# Sheet.net
KiCad netlist of a schematic drawn in Altium Designer
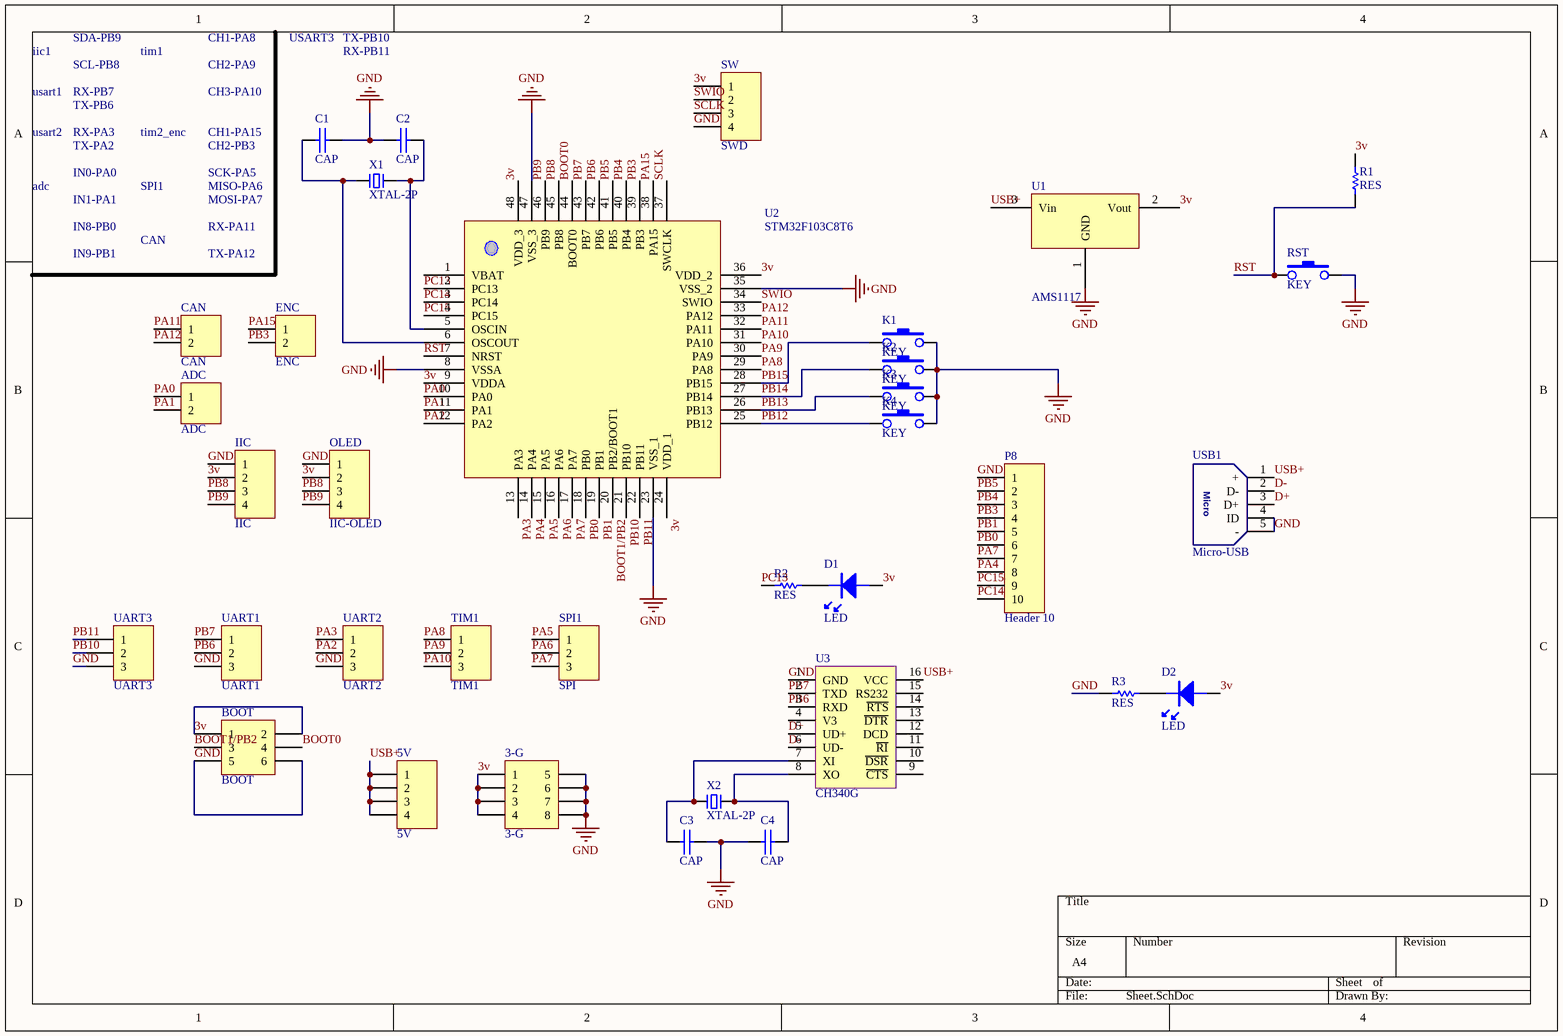
[diagram p0: Sheet.SchDoc]

(export (version "E")
  (design (tool "Eeschema 10.0.6"))
  (components
    (comp (ref "3-G")
      (value "3-G")
      (footprint "HDR2X4_CEN")
      (description "Header, 4-Pin, Dual row")
      (fields (field (name "PUBLISHER") "Altium Limited"))
      (libsource (lib "Miscellaneous Connectors") (part "Header 4X2A"))
    )
    (comp (ref "5V")
      (value "5V")
      (footprint "HDR1X4")
      (description "Header, 4-Pin")
      (fields (field (name "PUBLISHER") "Altium Limited"))
      (libsource (lib "Miscellaneous Connectors") (part "Header 4"))
    )
    (comp (ref "ADC")
      (value "ADC")
      (footprint "HDR1X2")
      (description "Header, 2-Pin")
      (fields (field (name "PUBLISHER") "Altium Limited"))
      (libsource (lib "Miscellaneous Connectors") (part "Header 2"))
    )
    (comp (ref "BOOT")
      (value "BOOT")
      (footprint "HDR2X3")
      (description "Header, 3-Pin, Dual row")
      (fields (field (name "PUBLISHER") "Altium Limited"))
      (libsource (lib "Miscellaneous Connectors") (part "Header 3X2"))
    )
    (comp (ref "C1")
      (value "CAP")
      (footprint "0603C")
      (description "无极性电容")
      (libsource (lib "电容") (part "CAP"))
    )
    (comp (ref "C2")
      (value "CAP")
      (footprint "0603C")
      (description "无极性电容")
      (libsource (lib "电容") (part "CAP"))
    )
    (comp (ref "C3")
      (value "CAP")
      (footprint "0603C")
      (description "无极性电容")
      (libsource (lib "电容") (part "CAP"))
    )
    (comp (ref "C4")
      (value "CAP")
      (footprint "0603C")
      (description "无极性电容")
      (libsource (lib "电容") (part "CAP"))
    )
    (comp (ref "CAN")
      (value "CAN")
      (footprint "HDR1X2")
      (description "Header, 2-Pin")
      (fields (field (name "PUBLISHER") "Altium Limited"))
      (libsource (lib "Miscellaneous Connectors") (part "Header 2"))
    )
    (comp (ref "D1") (value "LED") (footprint "LED-0603B") (libsource (lib "LED") (part "LED")))
    (comp (ref "D2") (value "LED") (footprint "LED-0603B") (libsource (lib "LED") (part "LED")))
    (comp (ref "ENC")
      (value "ENC")
      (footprint "HDR1X2")
      (description "Header, 2-Pin")
      (fields (field (name "PUBLISHER") "Altium Limited"))
      (libsource (lib "Miscellaneous Connectors") (part "Header 2"))
    )
    (comp (ref "IIC")
      (value "IIC")
      (footprint "HDR1X4")
      (description "Header, 4-Pin")
      (fields (field (name "PUBLISHER") "Altium Limited"))
      (libsource (lib "Miscellaneous Connectors") (part "Header 4"))
    )
    (comp (ref "K1") (value "KEY") (footprint "DIP-3X6X4.3") (libsource (lib "轻触开关") (part "KEY")))
    (comp (ref "K2") (value "KEY") (footprint "DIP-3X6X4.3") (libsource (lib "轻触开关") (part "KEY")))
    (comp (ref "K3") (value "KEY") (footprint "DIP-3X6X4.3") (libsource (lib "轻触开关") (part "KEY")))
    (comp (ref "K4") (value "KEY") (footprint "DIP-3X6X4.3") (libsource (lib "轻触开关") (part "KEY")))
    (comp (ref "OLED")
      (value "IIC-OLED")
      (footprint "HDR1X4")
      (description "Header, 4-Pin")
      (fields (field (name "PUBLISHER") "Altium Limited"))
      (libsource (lib "Miscellaneous Connectors") (part "Header 4"))
    )
    (comp (ref "P8")
      (value "Header 10")
      (footprint "HDR1X10")
      (description "Header, 10-Pin")
      (fields (field (name "PUBLISHER") "Altium Limited"))
      (libsource (lib "Miscellaneous Connectors") (part "Header 10"))
    )
    (comp (ref "R1") (value "RES") (footprint "0603R") (libsource (lib "电阻") (part "RES")))
    (comp (ref "R2") (value "RES") (footprint "0603R") (libsource (lib "电阻") (part "RES")))
    (comp (ref "R3") (value "RES") (footprint "0603R") (libsource (lib "电阻") (part "RES")))
    (comp (ref "RST") (value "KEY") (footprint "DIP-3X6X4.3") (libsource (lib "轻触开关") (part "KEY")))
    (comp (ref "SPI1")
      (value "SPI")
      (footprint "HDR1X3")
      (description "Header, 3-Pin")
      (fields (field (name "PUBLISHER") "Altium Limited"))
      (libsource (lib "Miscellaneous Connectors") (part "Header 3"))
    )
    (comp (ref "SW")
      (value "SWD")
      (footprint "HDR1X4")
      (description "Header, 4-Pin")
      (fields (field (name "PUBLISHER") "Altium Limited"))
      (libsource (lib "STM32F103C8T6") (part "Header 4"))
    )
    (comp (ref "TIM1")
      (value "TIM1")
      (footprint "HDR1X3")
      (description "Header, 3-Pin")
      (fields (field (name "PUBLISHER") "Altium Limited"))
      (libsource (lib "Miscellaneous Connectors") (part "Header 3"))
    )
    (comp (ref "U1")
      (value "AMS1117")
      (footprint "SOT223")
      (description "三端稳压芯片")
      (libsource (lib "电源芯片") (part "AMS1117"))
    )
    (comp (ref "U2")
      (value "STM32F103C8T6")
      (footprint "48P")
      (libsource (lib "STM32F103C8T6") (part "STM32F103C8T6"))
    )
    (comp (ref "U3") (value "CH340G") (footprint "SOP16") (libsource (lib "通讯系列IC") (part "CH340G")))
    (comp (ref "UART1")
      (value "UART1")
      (footprint "HDR1X3")
      (description "Header, 3-Pin")
      (fields (field (name "PUBLISHER") "Altium Limited"))
      (libsource (lib "Miscellaneous Connectors") (part "Header 3"))
    )
    (comp (ref "UART2")
      (value "UART2")
      (footprint "HDR1X3")
      (description "Header, 3-Pin")
      (fields (field (name "PUBLISHER") "Altium Limited"))
      (libsource (lib "Miscellaneous Connectors") (part "Header 3"))
    )
    (comp (ref "UART3")
      (value "UART3")
      (footprint "HDR1X3H")
      (description "Header, 3-Pin, Right Angle")
      (fields (field (name "PUBLISHER") "Altium Limited"))
      (libsource (lib "Miscellaneous Connectors") (part "Header 3H"))
    )
    (comp (ref "USB1")
      (value "Micro-USB")
      (footprint "USB-MICRO_A")
      (libsource (lib "USB") (part "Micro-USB"))
    )
    (comp (ref "X1")
      (value "XTAL-2P")
      (footprint "OSC HC-49S")
      (description "2脚无源脚晶振")
      (libsource (lib "晶振") (part "XTAL-2P"))
    )
    (comp (ref "X2")
      (value "XTAL-2P")
      (footprint "OSC HC-49S")
      (description "2脚无源脚晶振")
      (libsource (lib "晶振") (part "XTAL-2P"))
    )
  )
  (nets
    (net (code "1") (name "/3v") (class "Default")
      (node (ref "3-G") (pin "1") (pinfunction "1_1") (pintype "passive"))
      (node (ref "3-G") (pin "2") (pinfunction "2_2") (pintype "passive"))
      (node (ref "3-G") (pin "3") (pinfunction "3_3") (pintype "passive"))
      (node (ref "3-G") (pin "4") (pinfunction "4_4") (pintype "passive"))
      (node (ref "BOOT") (pin "1") (pinfunction "1_1") (pintype "passive"))
      (node (ref "BOOT") (pin "2") (pinfunction "2_2") (pintype "passive"))
      (node (ref "D1") (pin "A") (pinfunction "A_A") (pintype "passive"))
      (node (ref "D2") (pin "A") (pinfunction "A_A") (pintype "passive"))
      (node (ref "IIC") (pin "2") (pinfunction "2_2") (pintype "passive"))
      (node (ref "OLED") (pin "2") (pinfunction "2_2") (pintype "passive"))
      (node (ref "R1") (pin "2") (pinfunction "2_2") (pintype "passive"))
      (node (ref "SW") (pin "1") (pinfunction "1_1") (pintype "passive"))
      (node (ref "U1") (pin "2") (pinfunction "Vout_2") (pintype "passive"))
      (node (ref "U2") (pin "24") (pinfunction "VDD_1_24") (pintype "passive"))
      (node (ref "U2") (pin "36") (pinfunction "VDD_2_36") (pintype "passive"))
      (node (ref "U2") (pin "48") (pinfunction "VDD_3_48") (pintype "passive"))
      (node (ref "U2") (pin "9") (pinfunction "VDDA_9") (pintype "passive"))
    )
    (net (code "2") (name "/BOOT0") (class "Default")
      (node (ref "BOOT") (pin "4") (pinfunction "4_4") (pintype "passive"))
      (node (ref "U2") (pin "44") (pinfunction "BOOT0_44") (pintype "passive"))
    )
    (net (code "3") (name "/BOOT1{slash}PB2") (class "Default")
      (node (ref "BOOT") (pin "3") (pinfunction "3_3") (pintype "passive"))
      (node (ref "U2") (pin "20") (pinfunction "PB2/BOOT1_20") (pintype "passive"))
    )
    (net (code "4") (name "/D+") (class "Default")
      (node (ref "U3") (pin "5") (pinfunction "UD+_5") (pintype "passive"))
      (node (ref "USB1") (pin "3") (pinfunction "D+_3") (pintype "passive"))
    )
    (net (code "5") (name "/D-") (class "Default")
      (node (ref "U3") (pin "6") (pinfunction "UD-_6") (pintype "passive"))
      (node (ref "USB1") (pin "2") (pinfunction "D-_2") (pintype "passive"))
    )
    (net (code "6") (name "/PA0") (class "Default")
      (node (ref "ADC") (pin "1") (pinfunction "1_1") (pintype "passive"))
      (node (ref "U2") (pin "10") (pinfunction "PA0_10") (pintype "passive"))
    )
    (net (code "7") (name "/PA1") (class "Default")
      (node (ref "ADC") (pin "2") (pinfunction "2_2") (pintype "passive"))
      (node (ref "U2") (pin "11") (pinfunction "PA1_11") (pintype "passive"))
    )
    (net (code "8") (name "/PA2") (class "Default")
      (node (ref "U2") (pin "12") (pinfunction "PA2_12") (pintype "passive"))
      (node (ref "UART2") (pin "2") (pinfunction "2_2") (pintype "passive"))
    )
    (net (code "9") (name "/PA3") (class "Default")
      (node (ref "U2") (pin "13") (pinfunction "PA3_13") (pintype "passive"))
      (node (ref "UART2") (pin "1") (pinfunction "1_1") (pintype "passive"))
    )
    (net (code "10") (name "/PA4") (class "Default")
      (node (ref "P8") (pin "8") (pinfunction "8_8") (pintype "passive"))
      (node (ref "U2") (pin "14") (pinfunction "PA4_14") (pintype "passive"))
    )
    (net (code "11") (name "/PA5") (class "Default")
      (node (ref "SPI1") (pin "1") (pinfunction "1_1") (pintype "passive"))
      (node (ref "U2") (pin "15") (pinfunction "PA5_15") (pintype "passive"))
    )
    (net (code "12") (name "/PA6") (class "Default")
      (node (ref "SPI1") (pin "2") (pinfunction "2_2") (pintype "passive"))
      (node (ref "U2") (pin "16") (pinfunction "PA6_16") (pintype "passive"))
    )
    (net (code "13") (name "/PA7") (class "Default")
      (node (ref "P8") (pin "7") (pinfunction "7_7") (pintype "passive"))
      (node (ref "SPI1") (pin "3") (pinfunction "3_3") (pintype "passive"))
      (node (ref "U2") (pin "17") (pinfunction "PA7_17") (pintype "passive"))
    )
    (net (code "14") (name "/PA8") (class "Default")
      (node (ref "TIM1") (pin "1") (pinfunction "1_1") (pintype "passive"))
      (node (ref "U2") (pin "29") (pinfunction "PA8_29") (pintype "passive"))
    )
    (net (code "15") (name "/PA9") (class "Default")
      (node (ref "TIM1") (pin "2") (pinfunction "2_2") (pintype "passive"))
      (node (ref "U2") (pin "30") (pinfunction "PA9_30") (pintype "passive"))
    )
    (net (code "16") (name "/PA10") (class "Default")
      (node (ref "TIM1") (pin "3") (pinfunction "3_3") (pintype "passive"))
      (node (ref "U2") (pin "31") (pinfunction "PA10_31") (pintype "passive"))
    )
    (net (code "17") (name "/PA11") (class "Default")
      (node (ref "CAN") (pin "1") (pinfunction "1_1") (pintype "passive"))
      (node (ref "U2") (pin "32") (pinfunction "PA11_32") (pintype "passive"))
    )
    (net (code "18") (name "/PA12") (class "Default")
      (node (ref "CAN") (pin "2") (pinfunction "2_2") (pintype "passive"))
      (node (ref "U2") (pin "33") (pinfunction "PA12_33") (pintype "passive"))
    )
    (net (code "19") (name "/PA15") (class "Default")
      (node (ref "ENC") (pin "1") (pinfunction "1_1") (pintype "passive"))
      (node (ref "U2") (pin "38") (pinfunction "PA15_38") (pintype "passive"))
    )
    (net (code "20") (name "/PB0") (class "Default")
      (node (ref "P8") (pin "6") (pinfunction "6_6") (pintype "passive"))
      (node (ref "U2") (pin "18") (pinfunction "PB0_18") (pintype "passive"))
    )
    (net (code "21") (name "/PB1") (class "Default")
      (node (ref "P8") (pin "5") (pinfunction "5_5") (pintype "passive"))
      (node (ref "U2") (pin "19") (pinfunction "PB1_19") (pintype "passive"))
    )
    (net (code "22") (name "/PB3") (class "Default")
      (node (ref "ENC") (pin "2") (pinfunction "2_2") (pintype "passive"))
      (node (ref "P8") (pin "4") (pinfunction "4_4") (pintype "passive"))
      (node (ref "U2") (pin "39") (pinfunction "PB3_39") (pintype "passive"))
    )
    (net (code "23") (name "/PB4") (class "Default")
      (node (ref "P8") (pin "3") (pinfunction "3_3") (pintype "passive"))
      (node (ref "U2") (pin "40") (pinfunction "PB4_40") (pintype "passive"))
    )
    (net (code "24") (name "/PB5") (class "Default")
      (node (ref "P8") (pin "2") (pinfunction "2_2") (pintype "passive"))
      (node (ref "U2") (pin "41") (pinfunction "PB5_41") (pintype "passive"))
    )
    (net (code "25") (name "/PB6") (class "Default")
      (node (ref "U2") (pin "42") (pinfunction "PB6_42") (pintype "passive"))
      (node (ref "U3") (pin "3") (pinfunction "RXD_3") (pintype "passive"))
      (node (ref "UART1") (pin "2") (pinfunction "2_2") (pintype "passive"))
    )
    (net (code "26") (name "/PB7") (class "Default")
      (node (ref "U2") (pin "43") (pinfunction "PB7_43") (pintype "passive"))
      (node (ref "U3") (pin "2") (pinfunction "TXD_2") (pintype "passive"))
      (node (ref "UART1") (pin "1") (pinfunction "1_1") (pintype "passive"))
    )
    (net (code "27") (name "/PB8") (class "Default")
      (node (ref "IIC") (pin "3") (pinfunction "3_3") (pintype "passive"))
      (node (ref "OLED") (pin "3") (pinfunction "3_3") (pintype "passive"))
      (node (ref "U2") (pin "45") (pinfunction "PB8_45") (pintype "passive"))
    )
    (net (code "28") (name "/PB9") (class "Default")
      (node (ref "IIC") (pin "4") (pinfunction "4_4") (pintype "passive"))
      (node (ref "OLED") (pin "4") (pinfunction "4_4") (pintype "passive"))
      (node (ref "U2") (pin "46") (pinfunction "PB9_46") (pintype "passive"))
    )
    (net (code "29") (name "/PB10") (class "Default")
      (node (ref "U2") (pin "21") (pinfunction "PB10_21") (pintype "passive"))
      (node (ref "UART3") (pin "2") (pinfunction "2_2") (pintype "passive"))
    )
    (net (code "30") (name "/PB11") (class "Default")
      (node (ref "U2") (pin "22") (pinfunction "PB11_22") (pintype "passive"))
      (node (ref "UART3") (pin "1") (pinfunction "1_1") (pintype "passive"))
    )
    (net (code "31") (name "/PB12") (class "Default")
      (node (ref "K4") (pin "1") (pinfunction "1_1") (pintype "passive"))
      (node (ref "U2") (pin "25") (pinfunction "PB12_25") (pintype "passive"))
    )
    (net (code "32") (name "/PB13") (class "Default")
      (node (ref "K3") (pin "1") (pinfunction "1_1") (pintype "passive"))
      (node (ref "U2") (pin "26") (pinfunction "PB13_26") (pintype "passive"))
    )
    (net (code "33") (name "/PB14") (class "Default")
      (node (ref "K2") (pin "1") (pinfunction "1_1") (pintype "passive"))
      (node (ref "U2") (pin "27") (pinfunction "PB14_27") (pintype "passive"))
    )
    (net (code "34") (name "/PB15") (class "Default")
      (node (ref "K1") (pin "1") (pinfunction "1_1") (pintype "passive"))
      (node (ref "U2") (pin "28") (pinfunction "PB15_28") (pintype "passive"))
    )
    (net (code "35") (name "/PC13") (class "Default")
      (node (ref "R2") (pin "1") (pinfunction "1_1") (pintype "passive"))
      (node (ref "U2") (pin "2") (pinfunction "PC13_2") (pintype "passive"))
    )
    (net (code "36") (name "/PC14") (class "Default")
      (node (ref "P8") (pin "10") (pinfunction "10_10") (pintype "passive"))
      (node (ref "U2") (pin "3") (pinfunction "PC14_3") (pintype "passive"))
    )
    (net (code "37") (name "/PC15") (class "Default")
      (node (ref "P8") (pin "9") (pinfunction "9_9") (pintype "passive"))
      (node (ref "U2") (pin "4") (pinfunction "PC15_4") (pintype "passive"))
    )
    (net (code "38") (name "/RST") (class "Default")
      (node (ref "R1") (pin "1") (pinfunction "1_1") (pintype "passive"))
      (node (ref "RST") (pin "1") (pinfunction "1_1") (pintype "passive"))
      (node (ref "U2") (pin "7") (pinfunction "NRST_7") (pintype "passive"))
    )
    (net (code "39") (name "/SCLK") (class "Default")
      (node (ref "SW") (pin "3") (pinfunction "3_3") (pintype "passive"))
      (node (ref "U2") (pin "37") (pinfunction "SWCLK_37") (pintype "passive"))
    )
    (net (code "40") (name "/SWIO") (class "Default")
      (node (ref "SW") (pin "2") (pinfunction "2_2") (pintype "passive"))
      (node (ref "U2") (pin "34") (pinfunction "SWIO_34") (pintype "passive"))
    )
    (net (code "41") (name "/USB+") (class "Default")
      (node (ref "5V") (pin "1") (pinfunction "1_1") (pintype "passive"))
      (node (ref "5V") (pin "2") (pinfunction "2_2") (pintype "passive"))
      (node (ref "5V") (pin "3") (pinfunction "3_3") (pintype "passive"))
      (node (ref "5V") (pin "4") (pinfunction "4_4") (pintype "passive"))
      (node (ref "U1") (pin "3") (pinfunction "Vin_3") (pintype "passive"))
      (node (ref "U3") (pin "16") (pinfunction "VCC_16") (pintype "passive"))
      (node (ref "USB1") (pin "1") (pinfunction "+_1") (pintype "passive"))
    )
    (net (code "42") (name "GND") (class "Default")
      (node (ref "3-G") (pin "5") (pinfunction "5_5") (pintype "passive"))
      (node (ref "3-G") (pin "6") (pinfunction "6_6") (pintype "passive"))
      (node (ref "3-G") (pin "7") (pinfunction "7_7") (pintype "passive"))
      (node (ref "3-G") (pin "8") (pinfunction "8_8") (pintype "passive"))
      (node (ref "BOOT") (pin "5") (pinfunction "5_5") (pintype "passive"))
      (node (ref "BOOT") (pin "6") (pinfunction "6_6") (pintype "passive"))
      (node (ref "C1") (pin "1") (pinfunction "1_1") (pintype "passive"))
      (node (ref "C2") (pin "2") (pinfunction "2_2") (pintype "passive"))
      (node (ref "C3") (pin "2") (pinfunction "2_2") (pintype "passive"))
      (node (ref "C4") (pin "1") (pinfunction "1_1") (pintype "passive"))
      (node (ref "IIC") (pin "1") (pinfunction "1_1") (pintype "passive"))
      (node (ref "K1") (pin "3") (pinfunction "3_3") (pintype "passive"))
      (node (ref "K2") (pin "3") (pinfunction "3_3") (pintype "passive"))
      (node (ref "K3") (pin "3") (pinfunction "3_3") (pintype "passive"))
      (node (ref "K4") (pin "3") (pinfunction "3_3") (pintype "passive"))
      (node (ref "OLED") (pin "1") (pinfunction "1_1") (pintype "passive"))
      (node (ref "P8") (pin "1") (pinfunction "1_1") (pintype "passive"))
      (node (ref "R3") (pin "1") (pinfunction "1_1") (pintype "passive"))
      (node (ref "RST") (pin "3") (pinfunction "3_3") (pintype "passive"))
      (node (ref "SW") (pin "4") (pinfunction "4_4") (pintype "passive"))
      (node (ref "U1") (pin "1") (pinfunction "GND_1") (pintype "passive"))
      (node (ref "U2") (pin "23") (pinfunction "VSS_1_23") (pintype "passive"))
      (node (ref "U2") (pin "35") (pinfunction "VSS_2_35") (pintype "passive"))
      (node (ref "U2") (pin "47") (pinfunction "VSS_3_47") (pintype "passive"))
      (node (ref "U2") (pin "8") (pinfunction "VSSA_8") (pintype "passive"))
      (node (ref "U3") (pin "1") (pinfunction "GND_1") (pintype "passive"))
      (node (ref "UART1") (pin "3") (pinfunction "3_3") (pintype "passive"))
      (node (ref "UART2") (pin "3") (pinfunction "3_3") (pintype "passive"))
      (node (ref "UART3") (pin "3") (pinfunction "3_3") (pintype "passive"))
      (node (ref "USB1") (pin "4") (pinfunction "ID_4") (pintype "passive"))
      (node (ref "USB1") (pin "5") (pinfunction "-_5") (pintype "passive"))
    )
    (net (code "43") (name "Net-(D1-PadK)") (class "Default")
      (node (ref "D1") (pin "K") (pinfunction "K_K") (pintype "passive"))
      (node (ref "R2") (pin "2") (pinfunction "2_2") (pintype "passive"))
    )
    (net (code "44") (name "Net-(D2-PadK)") (class "Default")
      (node (ref "D2") (pin "K") (pinfunction "K_K") (pintype "passive"))
      (node (ref "R3") (pin "2") (pinfunction "2_2") (pintype "passive"))
    )
    (net (code "45") (name "Net-(U2-OSCIN)") (class "Default")
      (node (ref "C2") (pin "1") (pinfunction "1_1") (pintype "passive"))
      (node (ref "U2") (pin "5") (pinfunction "OSCIN_5") (pintype "passive"))
      (node (ref "X1") (pin "1") (pinfunction "1_1") (pintype "passive"))
    )
    (net (code "46") (name "Net-(U2-OSCOUT)") (class "Default")
      (node (ref "C1") (pin "2") (pinfunction "2_2") (pintype "passive"))
      (node (ref "U2") (pin "6") (pinfunction "OSCOUT_6") (pintype "passive"))
      (node (ref "X1") (pin "2") (pinfunction "2_2") (pintype "passive"))
    )
    (net (code "47") (name "Net-(U3-XI)") (class "Default")
      (node (ref "C3") (pin "1") (pinfunction "1_1") (pintype "passive"))
      (node (ref "U3") (pin "7") (pinfunction "XI_7") (pintype "passive"))
      (node (ref "X2") (pin "1") (pinfunction "1_1") (pintype "passive"))
    )
    (net (code "48") (name "Net-(U3-XO)") (class "Default")
      (node (ref "C4") (pin "2") (pinfunction "2_2") (pintype "passive"))
      (node (ref "U3") (pin "8") (pinfunction "XO_8") (pintype "passive"))
      (node (ref "X2") (pin "2") (pinfunction "2_2") (pintype "passive"))
    )
    (net (code "49") (name "unconnected-(U2-VBAT-Pad1)") (class "Default")
      (node (ref "U2") (pin "1") (pinfunction "VBAT_1") (pintype "passive"))
    )
    (net (code "50") (name "unconnected-(U3-DCD-Pad12)") (class "Default")
      (node (ref "U3") (pin "12") (pinfunction "DCD_12") (pintype "passive"))
    )
    (net (code "51") (name "unconnected-(U3-RS232-Pad15)") (class "Default")
      (node (ref "U3") (pin "15") (pinfunction "RS232_15") (pintype "passive"))
    )
    (net (code "52") (name "unconnected-(U3-V3-Pad4)") (class "Default")
      (node (ref "U3") (pin "4") (pinfunction "V3_4") (pintype "passive"))
    )
    (net (code "53") (name "unconnected-(U3-~{CTS}-Pad9)") (class "Default")
      (node (ref "U3") (pin "9") (pinfunction "~{CTS}_9") (pintype "passive"))
    )
    (net (code "54") (name "unconnected-(U3-~{DSR}-Pad10)") (class "Default")
      (node (ref "U3") (pin "10") (pinfunction "~{DSR}_10") (pintype "passive"))
    )
    (net (code "55") (name "unconnected-(U3-~{DTR}-Pad13)") (class "Default")
      (node (ref "U3") (pin "13") (pinfunction "~{DTR}_13") (pintype "passive"))
    )
    (net (code "56") (name "unconnected-(U3-~{RI}-Pad11)") (class "Default")
      (node (ref "U3") (pin "11") (pinfunction "~{RI}_11") (pintype "passive"))
    )
    (net (code "57") (name "unconnected-(U3-~{RTS}-Pad14)") (class "Default")
      (node (ref "U3") (pin "14") (pinfunction "~{RTS}_14") (pintype "passive"))
    )
  )
)
